# THUMB_CONNECTOR.net
KiCad netlist of a schematic drawn in Altium Designer
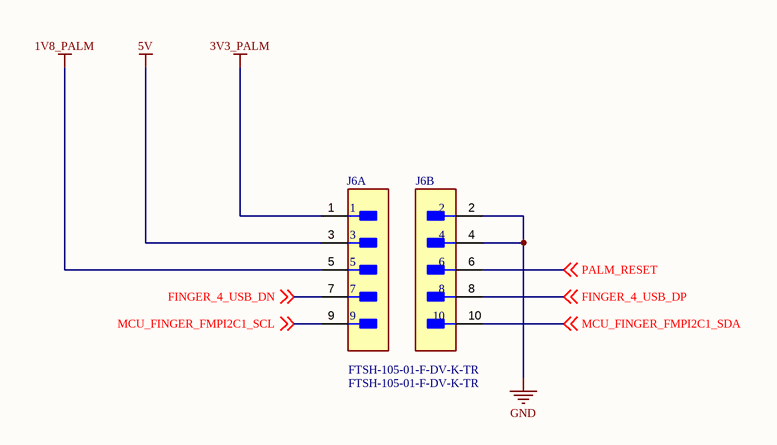
[diagram p0: THUMB_CONNECTOR.SchDoc]

(export (version "E")
  (design (tool "Eeschema 10.0.6"))
  (components
    (comp (ref "J6")
      (value "FTSH-105-01-F-DV-K-TR")
      (footprint "FP-FTSH-105-01-F-DV-K-TR-MFG")
      (description "CONN HEADER SMD 10POS 1.27MM")
      (libsource (lib "") (part "544f42128f4185dcb88ce1ce9bf1982_1"))
    )
  )
  (nets
    (net (code "1") (name "1V8_PALM") (class "Default")
      (node (ref "J6") (pin "5") (pinfunction "5_5") (pintype "passive"))
    )
    (net (code "2") (name "3V3_PALM") (class "Default")
      (node (ref "J6") (pin "1") (pinfunction "1_1") (pintype "passive"))
    )
    (net (code "3") (name "5V") (class "Default")
      (node (ref "J6") (pin "3") (pinfunction "3_3") (pintype "passive"))
    )
    (net (code "4") (name "FINGER_4_USB_DN") (class "Default")
      (node (ref "J6") (pin "7") (pinfunction "7_7") (pintype "passive"))
    )
    (net (code "5") (name "FINGER_4_USB_DP") (class "Default")
      (node (ref "J6") (pin "8") (pinfunction "8_8") (pintype "passive"))
    )
    (net (code "6") (name "GND") (class "Default")
      (node (ref "J6") (pin "2") (pinfunction "2_2") (pintype "passive"))
      (node (ref "J6") (pin "4") (pinfunction "4_4") (pintype "passive"))
    )
    (net (code "7") (name "MCU_FINGER_FMPI2C1_SCL") (class "Default")
      (node (ref "J6") (pin "9") (pinfunction "9_9") (pintype "passive"))
    )
    (net (code "8") (name "MCU_FINGER_FMPI2C1_SDA") (class "Default")
      (node (ref "J6") (pin "10") (pinfunction "10_10") (pintype "passive"))
    )
    (net (code "9") (name "PALM_RESET") (class "Default")
      (node (ref "J6") (pin "6") (pinfunction "6_6") (pintype "passive"))
    )
  )
)
